# MCU.net
KiCad netlist of a schematic drawn in Altium Designer
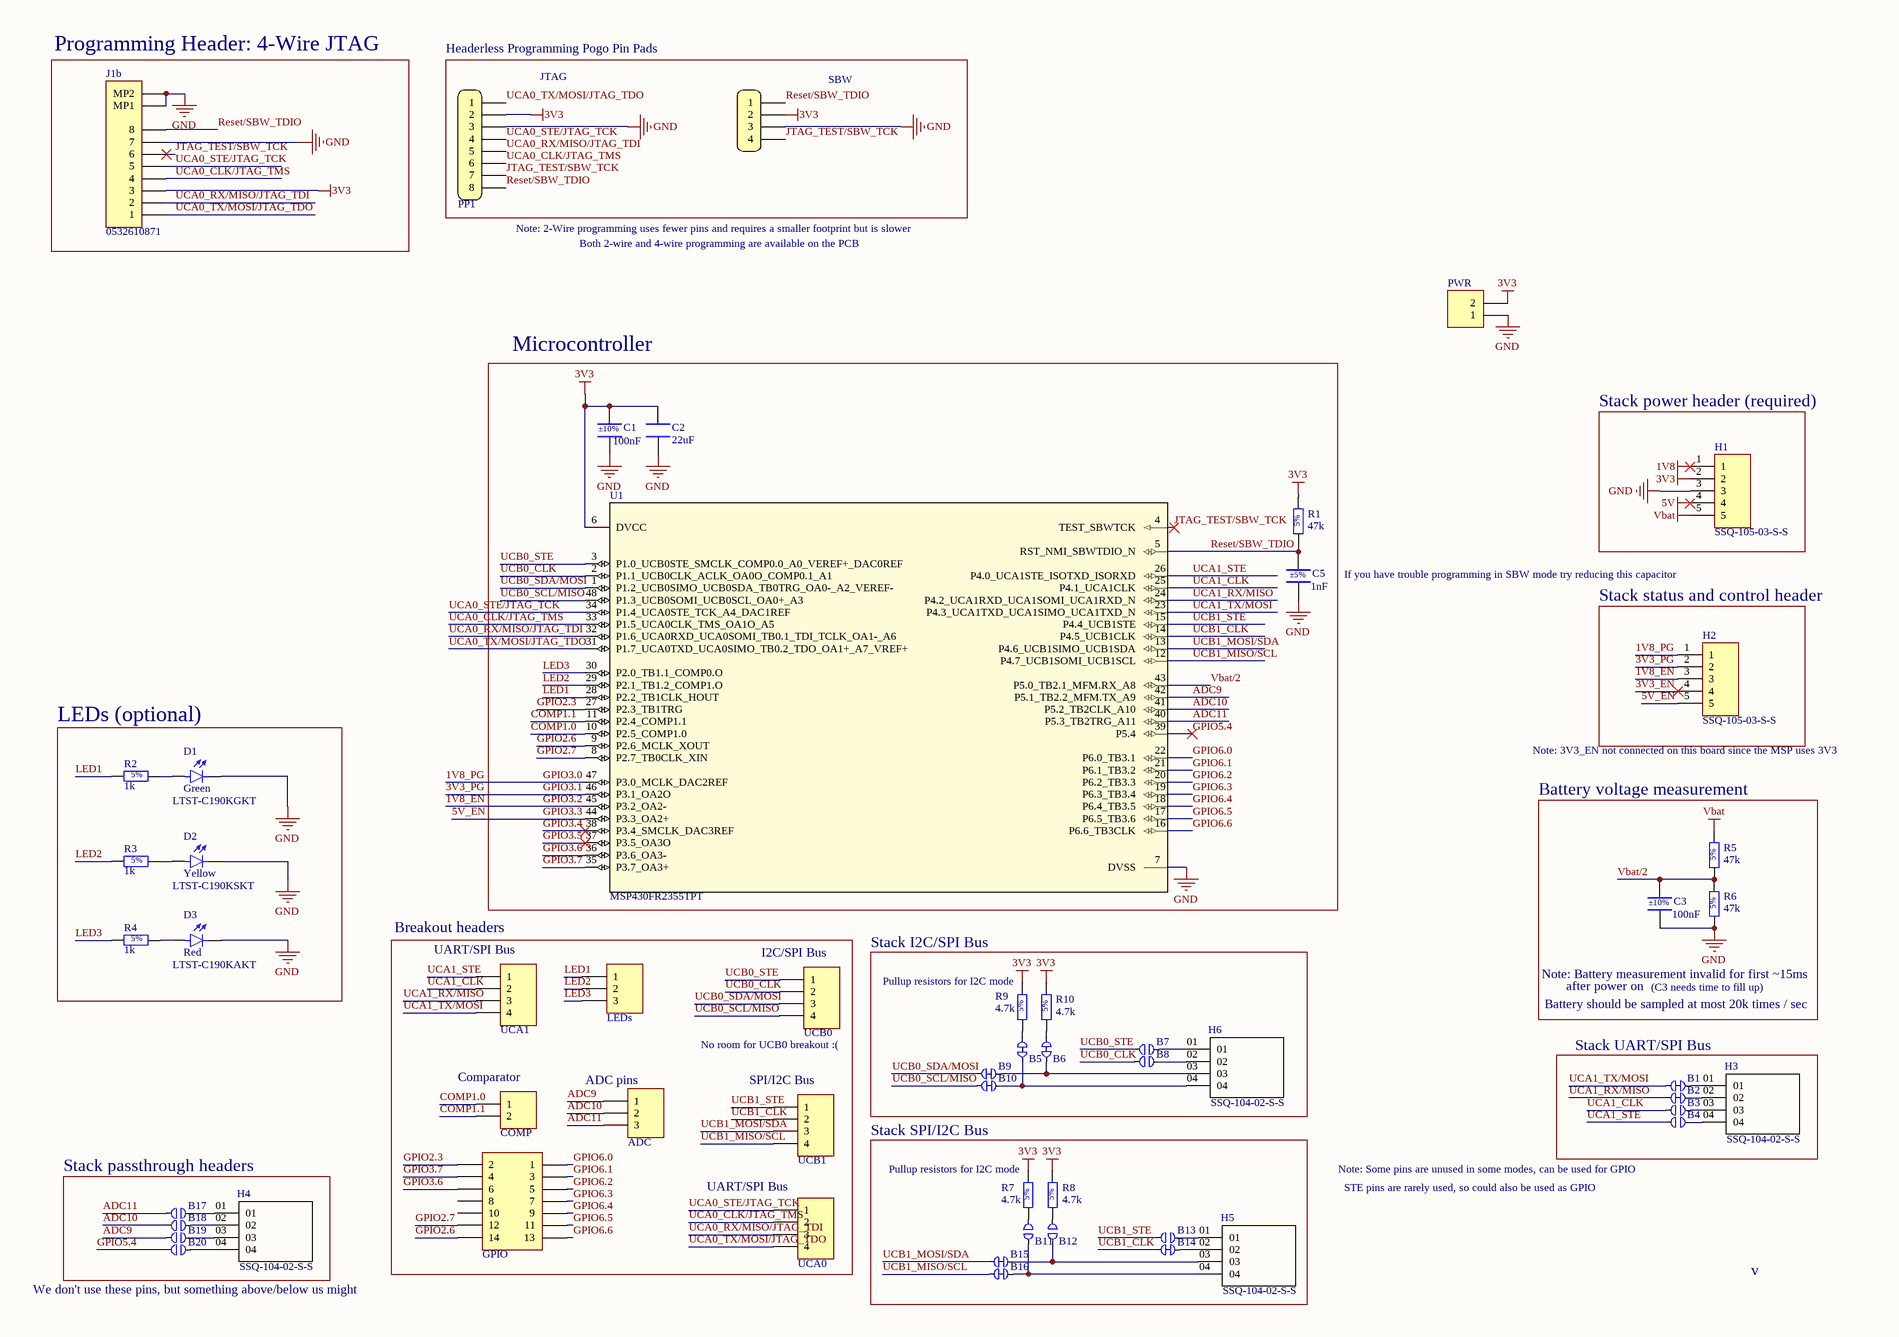
[diagram p0: MCU.SchDoc, left]
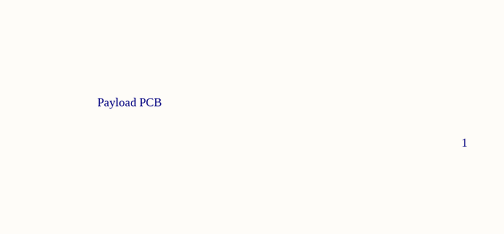
[diagram p1: MCU.SchDoc, right]

(export (version "E")
  (design (tool "Eeschema 10.0.6"))
  (components
    (comp (ref "ADC")
      (value "Header 3")
      (footprint "HDR1X3")
      (description "Header, 3-Pin")
      (libsource (lib "Miscellaneous Connectors") (part "Header 3"))
    )
    (comp (ref "B1")
      (value "Solder Jumper Normally Closed 0201")
      (footprint "Solder Bridge Closed 0201")
      (libsource (lib "APSS Generic Components") (part "Solder Jumper Normally Closed 0201"))
    )
    (comp (ref "B2")
      (value "Solder Jumper Normally Closed 0201")
      (footprint "Solder Bridge Closed 0201")
      (libsource (lib "APSS Generic Components") (part "Solder Jumper Normally Closed 0201"))
    )
    (comp (ref "B3")
      (value "Solder Jumper Normally Open 0201")
      (footprint "Solder Bridge Open 0201")
      (libsource (lib "APSS Generic Components") (part "Solder Jumper Normally Open 0201"))
    )
    (comp (ref "B4")
      (value "Solder Jumper Normally Open 0201")
      (footprint "Solder Bridge Open 0201")
      (libsource (lib "APSS Generic Components") (part "Solder Jumper Normally Open 0201"))
    )
    (comp (ref "B5")
      (value "Solder Jumper Normally Closed 0201")
      (footprint "Solder Bridge Closed 0201")
      (libsource (lib "APSS Generic Components") (part "Solder Jumper Normally Closed 0201"))
    )
    (comp (ref "B6")
      (value "Solder Jumper Normally Closed 0201")
      (footprint "Solder Bridge Closed 0201")
      (libsource (lib "APSS Generic Components") (part "Solder Jumper Normally Closed 0201"))
    )
    (comp (ref "B7")
      (value "Solder Jumper Normally Open 0201")
      (footprint "Solder Bridge Open 0201")
      (libsource (lib "") (part "Solder Jumper Normally Open 0201_1"))
    )
    (comp (ref "B8")
      (value "Solder Jumper Normally Open 0201")
      (footprint "Solder Bridge Open 0201")
      (libsource (lib "") (part "Solder Jumper Normally Open 0201_1"))
    )
    (comp (ref "B9")
      (value "Solder Jumper Normally Closed 0201")
      (footprint "Solder Bridge Closed 0201")
      (libsource (lib "APSS Generic Components") (part "Solder Jumper Normally Closed 0201"))
    )
    (comp (ref "B10")
      (value "Solder Jumper Normally Closed 0201")
      (footprint "Solder Bridge Closed 0201")
      (libsource (lib "APSS Generic Components") (part "Solder Jumper Normally Closed 0201"))
    )
    (comp (ref "B11")
      (value "Solder Jumper Normally Open 0201")
      (footprint "Solder Bridge Open 0201")
      (libsource (lib "APSS Generic Components") (part "Solder Jumper Normally Open 0201"))
    )
    (comp (ref "B12")
      (value "Solder Jumper Normally Open 0201")
      (footprint "Solder Bridge Open 0201")
      (libsource (lib "APSS Generic Components") (part "Solder Jumper Normally Open 0201"))
    )
    (comp (ref "B13")
      (value "Solder Jumper Normally Open 0201")
      (footprint "Solder Bridge Open 0201")
      (libsource (lib "APSS Generic Components") (part "Solder Jumper Normally Open 0201"))
    )
    (comp (ref "B14")
      (value "Solder Jumper Normally Closed 0201")
      (footprint "Solder Bridge Closed 0201")
      (libsource (lib "APSS Generic Components") (part "Solder Jumper Normally Closed 0201"))
    )
    (comp (ref "B15")
      (value "Solder Jumper Normally Closed 0201")
      (footprint "Solder Bridge Closed 0201")
      (libsource (lib "APSS Generic Components") (part "Solder Jumper Normally Closed 0201"))
    )
    (comp (ref "B16")
      (value "Solder Jumper Normally Closed 0201")
      (footprint "Solder Bridge Closed 0201")
      (libsource (lib "APSS Generic Components") (part "Solder Jumper Normally Closed 0201"))
    )
    (comp (ref "B17")
      (value "Solder Jumper Normally Open 0201")
      (footprint "Solder Bridge Open 0201")
      (libsource (lib "APSS Generic Components") (part "Solder Jumper Normally Open 0201"))
    )
    (comp (ref "B18")
      (value "Solder Jumper Normally Open 0201")
      (footprint "Solder Bridge Open 0201")
      (libsource (lib "APSS Generic Components") (part "Solder Jumper Normally Open 0201"))
    )
    (comp (ref "B19")
      (value "Solder Jumper Normally Open 0201")
      (footprint "Solder Bridge Open 0201")
      (libsource (lib "APSS Generic Components") (part "Solder Jumper Normally Open 0201"))
    )
    (comp (ref "B20")
      (value "Solder Jumper Normally Open 0201")
      (footprint "Solder Bridge Open 0201")
      (libsource (lib "APSS Generic Components") (part "Solder Jumper Normally Open 0201"))
    )
    (comp (ref "C1")
      (value "100nF")
      (footprint "APSS Generic Components:CAPACITOR_0805_2012M-70N")
      (description "Generic Capacitor")
      (fields (field (name "TOLERANCE") "±10%") (field (name "MF PART NO.") "C0805C104K5RAC7800"))
      (libsource (lib "General Components") (part "Generic Capacitor"))
    )
    (comp (ref "C2")
      (value "22uF")
      (footprint "APSS Prototype Parts:CAPACITOR_0805_2012M-70N")
      (description "Passive - Capacitor, X5R, 22uF Max, 6.3V, 0805 (2012 Metric), ±20%, -55°C ~ 85°C. 8.8uF @ 5V")
      (fields (field (name "TOLERANCE") "±20%") (field (name "MF PART NO.") "C0805C226M9PACTU"))
      (libsource (lib "APSS Prototype Parts") (part "C0805C226M9PACTU"))
    )
    (comp (ref "C3")
      (value "100nF")
      (footprint "APSS Generic Components:CAPACITOR_0805_2012M-70N")
      (description "Generic Capacitor")
      (fields (field (name "TOLERANCE") "±10%") (field (name "MF PART NO.") "C0805C104K5RAC7800"))
      (libsource (lib "APSS Generic Components") (part "Generic Capacitor"))
    )
    (comp (ref "C5")
      (value "1nF")
      (footprint "APSS Generic Components:CAPACITOR_0805_2012M-70N")
      (description "Generic Capacitor")
      (fields (field (name "TOLERANCE") "±5%") (field (name "MF PART NO.") "399-C0805C102J5GAC7800CT-ND"))
      (libsource (lib "APSS Generic Components") (part "Generic Capacitor"))
    )
    (comp (ref "COMP")
      (value "Header 2")
      (footprint "HDR1X2")
      (description "Header, 2-Pin")
      (libsource (lib "Miscellaneous Connectors") (part "Header 2"))
    )
    (comp (ref "D1")
      (value "LTST-C190 Series")
      (footprint "APSS Prototype Parts:LED_0603_1608M_0.80mm")
      (description "Diode - LED, 0603")
      (fields
        (field (name "MF PART NO.") "LTST-C190KGKT")
        (field (name "COLOUR") "Green")
        (field (name "APSS STANDARD PART") "APSS Standard")
      )
      (libsource (lib "APSS Prototype Parts") (part "LTST-C190 Series"))
    )
    (comp (ref "D2")
      (value "LTST-C190 Series")
      (footprint "APSS Prototype Parts:LED_0603_1608M_0.80mm")
      (description "Diode - LED, 0603")
      (fields
        (field (name "MF PART NO.") "LTST-C190KSKT")
        (field (name "COLOUR") "Yellow")
        (field (name "APSS STANDARD PART") "APSS Standard")
      )
      (libsource (lib "APSS Prototype Parts") (part "LTST-C190 Series"))
    )
    (comp (ref "D3")
      (value "LTST-C190 Series")
      (footprint "APSS Prototype Parts:LED_0603_1608M_0.80mm")
      (description "Diode - LED, 0603")
      (fields
        (field (name "MF PART NO.") "LTST-C190KAKT")
        (field (name "COLOUR") "Red")
        (field (name "APSS STANDARD PART") "APSS Standard")
      )
      (libsource (lib "APSS Prototype Parts") (part "LTST-C190 Series"))
    )
    (comp (ref "GPIO")
      (value "Header 7X2")
      (footprint "HDR2X7")
      (description "Header, 7-Pin, Dual row")
      (libsource (lib "Miscellaneous Connectors") (part "Header 7X2"))
    )
    (comp (ref "H1")
      (value "SSQ-105-03-S-S")
      (footprint "SAMTEC_SSQ-105-03-S-S:SAMTEC_SSQ-105-03-S-S")
      (libsource (lib "SSQ-105-03-S-S") (part "SSQ-105-03-S-S"))
    )
    (comp (ref "H2")
      (value "SSQ-105-03-S-S")
      (footprint "SAMTEC_SSQ-105-03-S-S:SAMTEC_SSQ-105-03-S-S")
      (libsource (lib "SSQ-105-03-S-S") (part "SSQ-105-03-S-S"))
    )
    (comp (ref "H3")
      (value "SSQ-104-02-S-S")
      (footprint "*SAMTEC_SSQ-104-02-S-S_SSQ-104-02-S-S(Primary)")
      (libsource (lib "SSQ-104-02-S-S") (part "SSQ-104-02-S-S"))
    )
    (comp (ref "H4")
      (value "SSQ-104-02-S-S")
      (footprint "*SAMTEC_SSQ-104-02-S-S_SSQ-104-02-S-S(Primary)")
      (libsource (lib "SSQ-104-02-S-S") (part "SSQ-104-02-S-S"))
    )
    (comp (ref "H5")
      (value "SSQ-104-02-S-S")
      (footprint "*SAMTEC_SSQ-104-02-S-S_SSQ-104-02-S-S(Primary)")
      (libsource (lib "SSQ-104-02-S-S") (part "SSQ-104-02-S-S"))
    )
    (comp (ref "H6")
      (value "SSQ-104-02-S-S")
      (footprint "*SAMTEC_SSQ-104-02-S-S_SSQ-104-02-S-S(Primary)")
      (libsource (lib "SSQ-104-02-S-S") (part "SSQ-104-02-S-S"))
    )
    (comp (ref "J1b")
      (value "0532610871")
      (footprint "APSS Prototype Parts:MOLEX_0532610871")
      (description "Header - Picoblade 08-pin, SMT, RA")
      (fields (field (name "MF PART NO.") "0532610871") (field (name "APSS STANDARD PART") "APSS Standard"))
      (libsource (lib "APSS Prototype Parts") (part "0532610871"))
    )
    (comp (ref "LEDs")
      (value "Header 3")
      (footprint "HDR1X3")
      (description "Header, 3-Pin")
      (libsource (lib "Miscellaneous Connectors") (part "Header 3"))
    )
    (comp (ref "PP1")
      (value "Headerless Pogo Holes 8-pin")
      (footprint "POGO_8_PIN_HEADER")
      (libsource (lib "APSS Generic Components") (part "Headerless Pogo Holes 8-pin"))
    )
    (comp (ref "PP2")
      (value "Headerless Pogo Holes 4-pin")
      (footprint "APSS Generic Components:POGO_4_PIN_HEADER")
      (libsource (lib "APSS Generic Components") (part "Headerless Pogo Holes 4-pin"))
    )
    (comp (ref "PWR")
      (value "~")
      (footprint "HDR1X2")
      (description "Header, 2-Pin")
      (libsource (lib "") (part "Header 2_1"))
    )
    (comp (ref "R1")
      (value "47k")
      (footprint "APSS Flight Parts:Resistor_0805_2012M-50N")
      (fields
        (field (name "TOLERANCE") "5%")
        (field (name "POWER") "1/8W")
        (field (name "MF PART NO.") "RMCF0805JT47K0")
      )
      (libsource (lib "APSS Prototype Parts") (part "RMCF0805JT Series"))
    )
    (comp (ref "R2")
      (value "1k")
      (footprint "APSS Flight Parts:Resistor_0805_2012M-50N")
      (fields
        (field (name "TOLERANCE") "5%")
        (field (name "POWER") "1/8W")
        (field (name "MF PART NO.") "RMCF0805JT1K00")
      )
      (libsource (lib "") (part "RMCF0805JT Series_1"))
    )
    (comp (ref "R3")
      (value "1k")
      (footprint "APSS Flight Parts:Resistor_0805_2012M-50N")
      (fields
        (field (name "TOLERANCE") "5%")
        (field (name "POWER") "1/8W")
        (field (name "MF PART NO.") "RMCF0805JT1K00")
      )
      (libsource (lib "") (part "RMCF0805JT Series_1"))
    )
    (comp (ref "R4")
      (value "1k")
      (footprint "APSS Flight Parts:Resistor_0805_2012M-50N")
      (fields
        (field (name "TOLERANCE") "5%")
        (field (name "POWER") "1/8W")
        (field (name "MF PART NO.") "RMCF0805JT1K00")
      )
      (libsource (lib "") (part "RMCF0805JT Series_1"))
    )
    (comp (ref "R5")
      (value "47k")
      (footprint "APSS Flight Parts:Resistor_0805_2012M-50N")
      (fields
        (field (name "TOLERANCE") "5%")
        (field (name "POWER") "1/8W")
        (field (name "MF PART NO.") "RMCF0805JT147K0")
      )
      (libsource (lib "APSS Prototype Parts") (part "RMCF0805JT Series"))
    )
    (comp (ref "R6")
      (value "47k")
      (footprint "APSS Flight Parts:Resistor_0805_2012M-50N")
      (fields
        (field (name "TOLERANCE") "5%")
        (field (name "POWER") "1/8W")
        (field (name "MF PART NO.") "RMCF0805JT47K0")
      )
      (libsource (lib "APSS Prototype Parts") (part "RMCF0805JT Series"))
    )
    (comp (ref "R7")
      (value "4.7k")
      (footprint "APSS Flight Parts:Resistor_0805_2012M-50N")
      (fields
        (field (name "TOLERANCE") "5%")
        (field (name "POWER") "1/8W")
        (field (name "MF PART NO.") "RMCF0805JT4K70")
      )
      (libsource (lib "APSS Prototype Parts") (part "RMCF0805JT Series"))
    )
    (comp (ref "R8")
      (value "4.7k")
      (footprint "APSS Flight Parts:Resistor_0805_2012M-50N")
      (fields
        (field (name "TOLERANCE") "5%")
        (field (name "POWER") "1/8W")
        (field (name "MF PART NO.") "RMCF0805JT4K70")
      )
      (libsource (lib "APSS Prototype Parts") (part "RMCF0805JT Series"))
    )
    (comp (ref "R9")
      (value "4.7k")
      (footprint "APSS Flight Parts:Resistor_0805_2012M-50N")
      (fields
        (field (name "TOLERANCE") "5%")
        (field (name "POWER") "1/8W")
        (field (name "MF PART NO.") "RMCF0805JT4K70")
      )
      (libsource (lib "APSS Prototype Parts") (part "RMCF0805JT Series"))
    )
    (comp (ref "R10")
      (value "4.7k")
      (footprint "APSS Flight Parts:Resistor_0805_2012M-50N")
      (fields
        (field (name "TOLERANCE") "5%")
        (field (name "POWER") "1/8W")
        (field (name "MF PART NO.") "RMCF0805JT4K70")
      )
      (libsource (lib "APSS Prototype Parts") (part "RMCF0805JT Series"))
    )
    (comp (ref "U1")
      (value "MSP430FR2355TPT")
      (footprint "PT0048A_L")
      (libsource (lib "MSP430") (part "MSP430FR2355IPT"))
    )
    (comp (ref "UCA0")
      (value "Header 4")
      (footprint "HDR1X4")
      (description "Header, 4-Pin")
      (libsource (lib "Miscellaneous Connectors") (part "Header 4"))
    )
    (comp (ref "UCA1")
      (value "Header 4")
      (footprint "HDR1X4")
      (description "Header, 4-Pin")
      (libsource (lib "Miscellaneous Connectors") (part "Header 4"))
    )
    (comp (ref "UCB0")
      (value "Header 4")
      (footprint "HDR1X4")
      (description "Header, 4-Pin")
      (libsource (lib "Miscellaneous Connectors") (part "Header 4"))
    )
    (comp (ref "UCB1")
      (value "Header 4")
      (footprint "HDR1X4")
      (description "Header, 4-Pin")
      (libsource (lib "Miscellaneous Connectors") (part "Header 4"))
    )
  )
  (nets
    (net (code "1") (name "/1V8_EN") (class "Default")
      (node (ref "H2") (pin "3") (pinfunction "3_3") (pintype "passive"))
      (node (ref "U1") (pin "45") (pinfunction "P3.2_OA2-_45") (pintype "bidirectional"))
    )
    (net (code "2") (name "/1V8_PG") (class "Default")
      (node (ref "H2") (pin "1") (pinfunction "1_1") (pintype "passive"))
      (node (ref "U1") (pin "47") (pinfunction "P3.0_MCLK_DAC2REF_47") (pintype "bidirectional"))
    )
    (net (code "3") (name "/3V3_EN") (class "Default")
      (node (ref "H2") (pin "4") (pinfunction "4_4") (pintype "passive+no_connect"))
    )
    (net (code "4") (name "/3V3_PG") (class "Default")
      (node (ref "H2") (pin "2") (pinfunction "2_2") (pintype "passive"))
      (node (ref "U1") (pin "46") (pinfunction "P3.1_OA2O_46") (pintype "bidirectional"))
    )
    (net (code "5") (name "/5V_EN") (class "Default")
      (node (ref "H2") (pin "5") (pinfunction "5_5") (pintype "passive"))
      (node (ref "U1") (pin "44") (pinfunction "P3.3_OA2+_44") (pintype "bidirectional"))
    )
    (net (code "7") (name "/ADC9") (class "Default")
      (node (ref "ADC") (pin "1") (pinfunction "1_1") (pintype "passive"))
      (node (ref "B19") (pin "1") (pinfunction "1_1") (pintype "passive"))
      (node (ref "U1") (pin "42") (pinfunction "P5.1_TB2.2_MFM.TX_A9_42") (pintype "bidirectional"))
    )
    (net (code "8") (name "/ADC10") (class "Default")
      (node (ref "ADC") (pin "2") (pinfunction "2_2") (pintype "passive"))
      (node (ref "B18") (pin "1") (pinfunction "1_1") (pintype "passive"))
      (node (ref "U1") (pin "41") (pinfunction "P5.2_TB2CLK_A10_41") (pintype "bidirectional"))
    )
    (net (code "9") (name "/ADC11") (class "Default")
      (node (ref "ADC") (pin "3") (pinfunction "3_3") (pintype "passive"))
      (node (ref "B17") (pin "1") (pinfunction "1_1") (pintype "passive"))
      (node (ref "U1") (pin "40") (pinfunction "P5.3_TB2TRG_A11_40") (pintype "bidirectional"))
    )
    (net (code "10") (name "/COMP1.0") (class "Default")
      (node (ref "COMP") (pin "1") (pinfunction "1_1") (pintype "passive"))
      (node (ref "U1") (pin "10") (pinfunction "P2.5_COMP1.0_10") (pintype "bidirectional"))
    )
    (net (code "11") (name "/COMP1.1") (class "Default")
      (node (ref "COMP") (pin "2") (pinfunction "2_2") (pintype "passive"))
      (node (ref "U1") (pin "11") (pinfunction "P2.4_COMP1.1_11") (pintype "bidirectional"))
    )
    (net (code "12") (name "/GPIO2.3") (class "Default")
      (node (ref "GPIO") (pin "2") (pinfunction "2_2") (pintype "passive"))
      (node (ref "U1") (pin "27") (pinfunction "P2.3_TB1TRG_27") (pintype "bidirectional"))
    )
    (net (code "13") (name "/GPIO2.6") (class "Default")
      (node (ref "GPIO") (pin "14") (pinfunction "14_14") (pintype "passive"))
      (node (ref "U1") (pin "9") (pinfunction "P2.6_MCLK_XOUT_9") (pintype "bidirectional"))
    )
    (net (code "14") (name "/GPIO2.7") (class "Default")
      (node (ref "GPIO") (pin "12") (pinfunction "12_12") (pintype "passive"))
      (node (ref "U1") (pin "8") (pinfunction "P2.7_TB0CLK_XIN_8") (pintype "bidirectional"))
    )
    (net (code "15") (name "/GPIO3.4") (class "Default")
      (node (ref "U1") (pin "38") (pinfunction "P3.4_SMCLK_DAC3REF_38") (pintype "bidirectional+no_connect"))
    )
    (net (code "16") (name "/GPIO3.5") (class "Default")
      (node (ref "U1") (pin "37") (pinfunction "P3.5_OA3O_37") (pintype "bidirectional+no_connect"))
    )
    (net (code "17") (name "/GPIO3.6") (class "Default")
      (node (ref "GPIO") (pin "6") (pinfunction "6_6") (pintype "passive"))
      (node (ref "U1") (pin "36") (pinfunction "P3.6_OA3-_36") (pintype "bidirectional"))
    )
    (net (code "18") (name "/GPIO3.7") (class "Default")
      (node (ref "GPIO") (pin "4") (pinfunction "4_4") (pintype "passive"))
      (node (ref "U1") (pin "35") (pinfunction "P3.7_OA3+_35") (pintype "bidirectional"))
    )
    (net (code "19") (name "/GPIO5.4") (class "Default")
      (node (ref "B20") (pin "1") (pinfunction "1_1") (pintype "passive"))
      (node (ref "U1") (pin "39") (pinfunction "P5.4_39") (pintype "bidirectional"))
    )
    (net (code "20") (name "/GPIO6.0") (class "Default")
      (node (ref "GPIO") (pin "1") (pinfunction "1_1") (pintype "passive"))
      (node (ref "U1") (pin "22") (pinfunction "P6.0_TB3.1_22") (pintype "bidirectional"))
    )
    (net (code "21") (name "/GPIO6.1") (class "Default")
      (node (ref "GPIO") (pin "3") (pinfunction "3_3") (pintype "passive"))
      (node (ref "U1") (pin "21") (pinfunction "P6.1_TB3.2_21") (pintype "bidirectional"))
    )
    (net (code "22") (name "/GPIO6.2") (class "Default")
      (node (ref "GPIO") (pin "5") (pinfunction "5_5") (pintype "passive"))
      (node (ref "U1") (pin "20") (pinfunction "P6.2_TB3.3_20") (pintype "bidirectional"))
    )
    (net (code "23") (name "/GPIO6.3") (class "Default")
      (node (ref "GPIO") (pin "7") (pinfunction "7_7") (pintype "passive"))
      (node (ref "U1") (pin "19") (pinfunction "P6.3_TB3.4_19") (pintype "bidirectional"))
    )
    (net (code "24") (name "/GPIO6.4") (class "Default")
      (node (ref "GPIO") (pin "9") (pinfunction "9_9") (pintype "passive"))
      (node (ref "U1") (pin "18") (pinfunction "P6.4_TB3.5_18") (pintype "bidirectional"))
    )
    (net (code "25") (name "/GPIO6.5") (class "Default")
      (node (ref "GPIO") (pin "11") (pinfunction "11_11") (pintype "passive"))
      (node (ref "U1") (pin "17") (pinfunction "P6.5_TB3.6_17") (pintype "bidirectional"))
    )
    (net (code "26") (name "/GPIO6.6") (class "Default")
      (node (ref "GPIO") (pin "13") (pinfunction "13_13") (pintype "passive"))
      (node (ref "U1") (pin "16") (pinfunction "P6.6_TB3CLK_16") (pintype "bidirectional"))
    )
    (net (code "27") (name "/JTAG_TEST{slash}SBW_TCK") (class "Default")
      (node (ref "J1b") (pin "6") (pinfunction "6_6") (pintype "passive"))
      (node (ref "PP1") (pin "7") (pinfunction "7_7") (pintype "passive"))
      (node (ref "PP2") (pin "4") (pinfunction "4_4") (pintype "passive"))
      (node (ref "U1") (pin "4") (pinfunction "TEST_SBWTCK_4") (pintype "input"))
    )
    (net (code "28") (name "/LED1") (class "Default")
      (node (ref "LEDs") (pin "1") (pinfunction "1_1") (pintype "passive"))
      (node (ref "R2") (pin "1") (pinfunction "1_1") (pintype "passive"))
      (node (ref "U1") (pin "28") (pinfunction "P2.2_TB1CLK_HOUT_28") (pintype "bidirectional"))
    )
    (net (code "29") (name "/LED2") (class "Default")
      (node (ref "LEDs") (pin "2") (pinfunction "2_2") (pintype "passive"))
      (node (ref "R3") (pin "1") (pinfunction "1_1") (pintype "passive"))
      (node (ref "U1") (pin "29") (pinfunction "P2.1_TB1.2_COMP1.O_29") (pintype "bidirectional"))
    )
    (net (code "30") (name "/LED3") (class "Default")
      (node (ref "LEDs") (pin "3") (pinfunction "3_3") (pintype "passive"))
      (node (ref "R4") (pin "1") (pinfunction "1_1") (pintype "passive"))
      (node (ref "U1") (pin "30") (pinfunction "P2.0_TB1.1_COMP0.O_30") (pintype "bidirectional"))
    )
    (net (code "31") (name "/Reset{slash}SBW_TDIO") (class "Default")
      (node (ref "C5") (pin "2") (pinfunction "2_2") (pintype "passive"))
      (node (ref "J1b") (pin "8") (pinfunction "8_8") (pintype "passive"))
      (node (ref "PP1") (pin "8") (pinfunction "8_8") (pintype "passive"))
      (node (ref "PP2") (pin "1") (pinfunction "1_1") (pintype "passive"))
      (node (ref "R1") (pin "1") (pinfunction "1_1") (pintype "passive"))
      (node (ref "U1") (pin "5") (pinfunction "RST_NMI_SBWTDIO_N_5") (pintype "bidirectional"))
    )
    (net (code "32") (name "/UCA0_CLK{slash}JTAG_TMS") (class "Default")
      (node (ref "J1b") (pin "4") (pinfunction "4_4") (pintype "passive"))
      (node (ref "PP1") (pin "6") (pinfunction "6_6") (pintype "passive"))
      (node (ref "U1") (pin "33") (pinfunction "P1.5_UCA0CLK_TMS_OA1O_A5_33") (pintype "bidirectional"))
      (node (ref "UCA0") (pin "2") (pinfunction "2_2") (pintype "passive"))
    )
    (net (code "33") (name "/UCA0_RX{slash}MISO{slash}JTAG_TDI") (class "Default")
      (node (ref "J1b") (pin "2") (pinfunction "2_2") (pintype "passive"))
      (node (ref "PP1") (pin "5") (pinfunction "5_5") (pintype "passive"))
      (node (ref "U1") (pin "32") (pinfunction "P1.6_UCA0RXD_UCA0SOMI_TB0.1_TDI_TCLK_OA1-_A6_32") (pintype "bidirectional"))
      (node (ref "UCA0") (pin "3") (pinfunction "3_3") (pintype "passive"))
    )
    (net (code "34") (name "/UCA0_STE{slash}JTAG_TCK") (class "Default")
      (node (ref "J1b") (pin "5") (pinfunction "5_5") (pintype "passive"))
      (node (ref "PP1") (pin "4") (pinfunction "4_4") (pintype "passive"))
      (node (ref "U1") (pin "34") (pinfunction "P1.4_UCA0STE_TCK_A4_DAC1REF_34") (pintype "bidirectional"))
      (node (ref "UCA0") (pin "1") (pinfunction "1_1") (pintype "passive"))
    )
    (net (code "35") (name "/UCA0_TX{slash}MOSI{slash}JTAG_TDO") (class "Default")
      (node (ref "J1b") (pin "1") (pinfunction "1_1") (pintype "passive"))
      (node (ref "PP1") (pin "1") (pinfunction "1_1") (pintype "passive"))
      (node (ref "U1") (pin "31") (pinfunction "P1.7_UCA0TXD_UCA0SIMO_TB0.2_TDO_OA1+_A7_VREF+_31") (pintype "bidirectional"))
      (node (ref "UCA0") (pin "4") (pinfunction "4_4") (pintype "passive"))
    )
    (net (code "36") (name "/UCA1_CLK") (class "Default")
      (node (ref "B3") (pin "1") (pinfunction "1_1") (pintype "passive"))
      (node (ref "U1") (pin "25") (pinfunction "P4.1_UCA1CLK_25") (pintype "bidirectional"))
      (node (ref "UCA1") (pin "2") (pinfunction "2_2") (pintype "passive"))
    )
    (net (code "37") (name "/UCA1_RX{slash}MISO") (class "Default")
      (node (ref "B2") (pin "1") (pinfunction "1_1") (pintype "passive"))
      (node (ref "U1") (pin "24") (pinfunction "P4.2_UCA1RXD_UCA1SOMI_UCA1RXD_N_24") (pintype "bidirectional"))
      (node (ref "UCA1") (pin "3") (pinfunction "3_3") (pintype "passive"))
    )
    (net (code "38") (name "/UCA1_STE") (class "Default")
      (node (ref "B4") (pin "1") (pinfunction "1_1") (pintype "passive"))
      (node (ref "U1") (pin "26") (pinfunction "P4.0_UCA1STE_ISOTXD_ISORXD_26") (pintype "bidirectional"))
      (node (ref "UCA1") (pin "1") (pinfunction "1_1") (pintype "passive"))
    )
    (net (code "39") (name "/UCA1_TX{slash}MOSI") (class "Default")
      (node (ref "B1") (pin "1") (pinfunction "1_1") (pintype "passive"))
      (node (ref "U1") (pin "23") (pinfunction "P4.3_UCA1TXD_UCA1SIMO_UCA1TXD_N_23") (pintype "bidirectional"))
      (node (ref "UCA1") (pin "4") (pinfunction "4_4") (pintype "passive"))
    )
    (net (code "40") (name "/UCB0_CLK") (class "Default")
      (node (ref "B8") (pin "2") (pinfunction "2_2") (pintype "passive"))
      (node (ref "U1") (pin "2") (pinfunction "P1.1_UCB0CLK_ACLK_OA0O_COMP0.1_A1_2") (pintype "bidirectional"))
      (node (ref "UCB0") (pin "2") (pinfunction "2_2") (pintype "passive"))
    )
    (net (code "41") (name "/UCB0_SCL{slash}MISO") (class "Default")
      (node (ref "B10") (pin "1") (pinfunction "1_1") (pintype "passive"))
      (node (ref "U1") (pin "48") (pinfunction "P1.3_UCB0SOMI_UCB0SCL_OA0+_A3_48") (pintype "bidirectional"))
      (node (ref "UCB0") (pin "4") (pinfunction "4_4") (pintype "passive"))
    )
    (net (code "42") (name "/UCB0_SDA{slash}MOSI") (class "Default")
      (node (ref "B9") (pin "2") (pinfunction "2_2") (pintype "passive"))
      (node (ref "U1") (pin "1") (pinfunction "P1.2_UCB0SIMO_UCB0SDA_TB0TRG_OA0-_A2_VEREF-_1") (pintype "bidirectional"))
      (node (ref "UCB0") (pin "3") (pinfunction "3_3") (pintype "passive"))
    )
    (net (code "43") (name "/UCB0_STE") (class "Default")
      (node (ref "B7") (pin "2") (pinfunction "2_2") (pintype "passive"))
      (node (ref "U1") (pin "3") (pinfunction "P1.0_UCB0STE_SMCLK_COMP0.0_A0_VEREF+_DAC0REF_3") (pintype "bidirectional"))
      (node (ref "UCB0") (pin "1") (pinfunction "1_1") (pintype "passive"))
    )
    (net (code "44") (name "/UCB1_CLK") (class "Default")
      (node (ref "B14") (pin "1") (pinfunction "1_1") (pintype "passive"))
      (node (ref "U1") (pin "14") (pinfunction "P4.5_UCB1CLK_14") (pintype "bidirectional"))
      (node (ref "UCB1") (pin "2") (pinfunction "2_2") (pintype "passive"))
    )
    (net (code "45") (name "/UCB1_MISO{slash}SCL") (class "Default")
      (node (ref "B16") (pin "1") (pinfunction "1_1") (pintype "passive"))
      (node (ref "U1") (pin "12") (pinfunction "P4.7_UCB1SOMI_UCB1SCL_12") (pintype "bidirectional"))
      (node (ref "UCB1") (pin "4") (pinfunction "4_4") (pintype "passive"))
    )
    (net (code "46") (name "/UCB1_MOSI{slash}SDA") (class "Default")
      (node (ref "B15") (pin "1") (pinfunction "1_1") (pintype "passive"))
      (node (ref "U1") (pin "13") (pinfunction "P4.6_UCB1SIMO_UCB1SDA_13") (pintype "bidirectional"))
      (node (ref "UCB1") (pin "3") (pinfunction "3_3") (pintype "passive"))
    )
    (net (code "47") (name "/UCB1_STE") (class "Default")
      (node (ref "B13") (pin "1") (pinfunction "1_1") (pintype "passive"))
      (node (ref "U1") (pin "15") (pinfunction "P4.4_UCB1STE_15") (pintype "bidirectional"))
      (node (ref "UCB1") (pin "1") (pinfunction "1_1") (pintype "passive"))
    )
    (net (code "48") (name "/Vbat{slash}2") (class "Default")
      (node (ref "C3") (pin "2") (pinfunction "2_2") (pintype "passive"))
      (node (ref "R5") (pin "1") (pinfunction "1_1") (pintype "passive"))
      (node (ref "R6") (pin "2") (pinfunction "2_2") (pintype "passive"))
      (node (ref "U1") (pin "43") (pinfunction "P5.0_TB2.1_MFM.RX_A8_43") (pintype "bidirectional"))
    )
    (net (code "49") (name "1V8") (class "Default")
      (node (ref "H1") (pin "1") (pinfunction "1_1") (pintype "passive"))
    )
    (net (code "50") (name "3V3") (class "Default")
      (node (ref "C1") (pin "2") (pinfunction "2_2") (pintype "passive"))
      (node (ref "C2") (pin "2") (pinfunction "2_2") (pintype "passive"))
      (node (ref "H1") (pin "2") (pinfunction "2_2") (pintype "passive"))
      (node (ref "J1b") (pin "3") (pinfunction "3_3") (pintype "passive"))
      (node (ref "PP1") (pin "2") (pinfunction "2_2") (pintype "passive"))
      (node (ref "PP2") (pin "2") (pinfunction "2_2") (pintype "passive"))
      (node (ref "PWR") (pin "2") (pinfunction "2_2") (pintype "passive"))
      (node (ref "R1") (pin "2") (pinfunction "2_2") (pintype "passive"))
      (node (ref "R10") (pin "2") (pinfunction "2_2") (pintype "passive"))
      (node (ref "R7") (pin "2") (pinfunction "2_2") (pintype "passive"))
      (node (ref "R8") (pin "2") (pinfunction "2_2") (pintype "passive"))
      (node (ref "R9") (pin "2") (pinfunction "2_2") (pintype "passive"))
      (node (ref "U1") (pin "6") (pinfunction "DVCC_6") (pintype "power_in"))
    )
    (net (code "51") (name "5V") (class "Default")
      (node (ref "H1") (pin "4") (pinfunction "4_4") (pintype "passive"))
    )
    (net (code "52") (name "GND") (class "Default")
      (node (ref "C1") (pin "1") (pinfunction "1_1") (pintype "passive"))
      (node (ref "C2") (pin "1") (pinfunction "1_1") (pintype "passive"))
      (node (ref "C3") (pin "1") (pinfunction "1_1") (pintype "passive"))
      (node (ref "C5") (pin "1") (pinfunction "1_1") (pintype "passive"))
      (node (ref "D1") (pin "C") (pinfunction "C_C") (pintype "passive"))
      (node (ref "D2") (pin "C") (pinfunction "C_C") (pintype "passive"))
      (node (ref "D3") (pin "C") (pinfunction "C_C") (pintype "passive"))
      (node (ref "H1") (pin "3") (pinfunction "3_3") (pintype "passive"))
      (node (ref "J1b") (pin "7") (pinfunction "7_7") (pintype "passive"))
      (node (ref "J1b") (pin "MP1") (pinfunction "MP1_MP1") (pintype "passive"))
      (node (ref "J1b") (pin "MP2") (pinfunction "MP2_MP2") (pintype "passive"))
      (node (ref "PP1") (pin "3") (pinfunction "3_3") (pintype "passive"))
      (node (ref "PP2") (pin "3") (pinfunction "3_3") (pintype "passive"))
      (node (ref "PWR") (pin "1") (pinfunction "1_1") (pintype "passive"))
      (node (ref "R6") (pin "1") (pinfunction "1_1") (pintype "passive"))
      (node (ref "U1") (pin "7") (pinfunction "DVSS_7") (pintype "power_in"))
    )
    (net (code "53") (name "Net-(B1-Pad2)") (class "Default")
      (node (ref "B1") (pin "2") (pinfunction "2_2") (pintype "passive"))
      (node (ref "H3") (pin "01") (pinfunction "01_01") (pintype "passive"))
    )
    (net (code "54") (name "Net-(B2-Pad2)") (class "Default")
      (node (ref "B2") (pin "2") (pinfunction "2_2") (pintype "passive"))
      (node (ref "H3") (pin "02") (pinfunction "02_02") (pintype "passive"))
    )
    (net (code "55") (name "Net-(B3-Pad2)") (class "Default")
      (node (ref "B3") (pin "2") (pinfunction "2_2") (pintype "passive"))
      (node (ref "H3") (pin "03") (pinfunction "03_03") (pintype "passive"))
    )
    (net (code "56") (name "Net-(B4-Pad2)") (class "Default")
      (node (ref "B4") (pin "2") (pinfunction "2_2") (pintype "passive"))
      (node (ref "H3") (pin "04") (pinfunction "04_04") (pintype "passive"))
    )
    (net (code "57") (name "Net-(B5-Pad2)") (class "Default")
      (node (ref "B5") (pin "2") (pinfunction "2_2") (pintype "passive"))
      (node (ref "R9") (pin "1") (pinfunction "1_1") (pintype "passive"))
    )
    (net (code "58") (name "Net-(B6-Pad1)") (class "Default")
      (node (ref "B6") (pin "1") (pinfunction "1_1") (pintype "passive"))
      (node (ref "R10") (pin "1") (pinfunction "1_1") (pintype "passive"))
    )
    (net (code "59") (name "Net-(B6-Pad2)") (class "Default")
      (node (ref "B6") (pin "2") (pinfunction "2_2") (pintype "passive"))
      (node (ref "B9") (pin "1") (pinfunction "1_1") (pintype "passive"))
      (node (ref "H6") (pin "03") (pinfunction "03_03") (pintype "passive"))
    )
    (net (code "60") (name "Net-(B7-Pad1)") (class "Default")
      (node (ref "B7") (pin "1") (pinfunction "1_1") (pintype "passive"))
      (node (ref "H6") (pin "01") (pinfunction "01_01") (pintype "passive"))
    )
    (net (code "61") (name "Net-(B8-Pad1)") (class "Default")
      (node (ref "B8") (pin "1") (pinfunction "1_1") (pintype "passive"))
      (node (ref "H6") (pin "02") (pinfunction "02_02") (pintype "passive"))
    )
    (net (code "62") (name "Net-(B10-Pad2)") (class "Default")
      (node (ref "B10") (pin "2") (pinfunction "2_2") (pintype "passive"))
      (node (ref "B5") (pin "1") (pinfunction "1_1") (pintype "passive"))
      (node (ref "H6") (pin "04") (pinfunction "04_04") (pintype "passive"))
    )
    (net (code "63") (name "Net-(B11-Pad1)") (class "Default")
      (node (ref "B11") (pin "1") (pinfunction "1_1") (pintype "passive"))
      (node (ref "B16") (pin "2") (pinfunction "2_2") (pintype "passive"))
      (node (ref "H5") (pin "04") (pinfunction "04_04") (pintype "passive"))
    )
    (net (code "64") (name "Net-(B11-Pad2)") (class "Default")
      (node (ref "B11") (pin "2") (pinfunction "2_2") (pintype "passive"))
      (node (ref "R7") (pin "1") (pinfunction "1_1") (pintype "passive"))
    )
    (net (code "65") (name "Net-(B12-Pad1)") (class "Default")
      (node (ref "B12") (pin "1") (pinfunction "1_1") (pintype "passive"))
      (node (ref "R8") (pin "1") (pinfunction "1_1") (pintype "passive"))
    )
    (net (code "66") (name "Net-(B12-Pad2)") (class "Default")
      (node (ref "B12") (pin "2") (pinfunction "2_2") (pintype "passive"))
      (node (ref "B15") (pin "2") (pinfunction "2_2") (pintype "passive"))
      (node (ref "H5") (pin "03") (pinfunction "03_03") (pintype "passive"))
    )
    (net (code "67") (name "Net-(B13-Pad2)") (class "Default")
      (node (ref "B13") (pin "2") (pinfunction "2_2") (pintype "passive"))
      (node (ref "H5") (pin "01") (pinfunction "01_01") (pintype "passive"))
    )
    (net (code "68") (name "Net-(B14-Pad2)") (class "Default")
      (node (ref "B14") (pin "2") (pinfunction "2_2") (pintype "passive"))
      (node (ref "H5") (pin "02") (pinfunction "02_02") (pintype "passive"))
    )
    (net (code "69") (name "Net-(B17-Pad2)") (class "Default")
      (node (ref "B17") (pin "2") (pinfunction "2_2") (pintype "passive"))
      (node (ref "H4") (pin "01") (pinfunction "01_01") (pintype "passive"))
    )
    (net (code "70") (name "Net-(B18-Pad2)") (class "Default")
      (node (ref "B18") (pin "2") (pinfunction "2_2") (pintype "passive"))
      (node (ref "H4") (pin "02") (pinfunction "02_02") (pintype "passive"))
    )
    (net (code "71") (name "Net-(B19-Pad2)") (class "Default")
      (node (ref "B19") (pin "2") (pinfunction "2_2") (pintype "passive"))
      (node (ref "H4") (pin "03") (pinfunction "03_03") (pintype "passive"))
    )
    (net (code "72") (name "Net-(B20-Pad2)") (class "Default")
      (node (ref "B20") (pin "2") (pinfunction "2_2") (pintype "passive"))
      (node (ref "H4") (pin "04") (pinfunction "04_04") (pintype "passive"))
    )
    (net (code "73") (name "Net-(D1-PadA)") (class "Default")
      (node (ref "D1") (pin "A") (pinfunction "A_A") (pintype "passive"))
      (node (ref "R2") (pin "2") (pinfunction "2_2") (pintype "passive"))
    )
    (net (code "74") (name "Net-(D2-PadA)") (class "Default")
      (node (ref "D2") (pin "A") (pinfunction "A_A") (pintype "passive"))
      (node (ref "R3") (pin "2") (pinfunction "2_2") (pintype "passive"))
    )
    (net (code "75") (name "Net-(D3-PadA)") (class "Default")
      (node (ref "D3") (pin "A") (pinfunction "A_A") (pintype "passive"))
      (node (ref "R4") (pin "2") (pinfunction "2_2") (pintype "passive"))
    )
    (net (code "76") (name "Vbat") (class "Default")
      (node (ref "H1") (pin "5") (pinfunction "5_5") (pintype "passive"))
      (node (ref "R5") (pin "2") (pinfunction "2_2") (pintype "passive"))
    )
    (net (code "77") (name "unconnected-(GPIO-Pad8)") (class "Default")
      (node (ref "GPIO") (pin "8") (pinfunction "8_8") (pintype "passive"))
    )
    (net (code "78") (name "unconnected-(GPIO-Pad10)") (class "Default")
      (node (ref "GPIO") (pin "10") (pinfunction "10_10") (pintype "passive"))
    )
  )
)
